# watchwinder.net
KiCad netlist of a schematic drawn in EAGLE
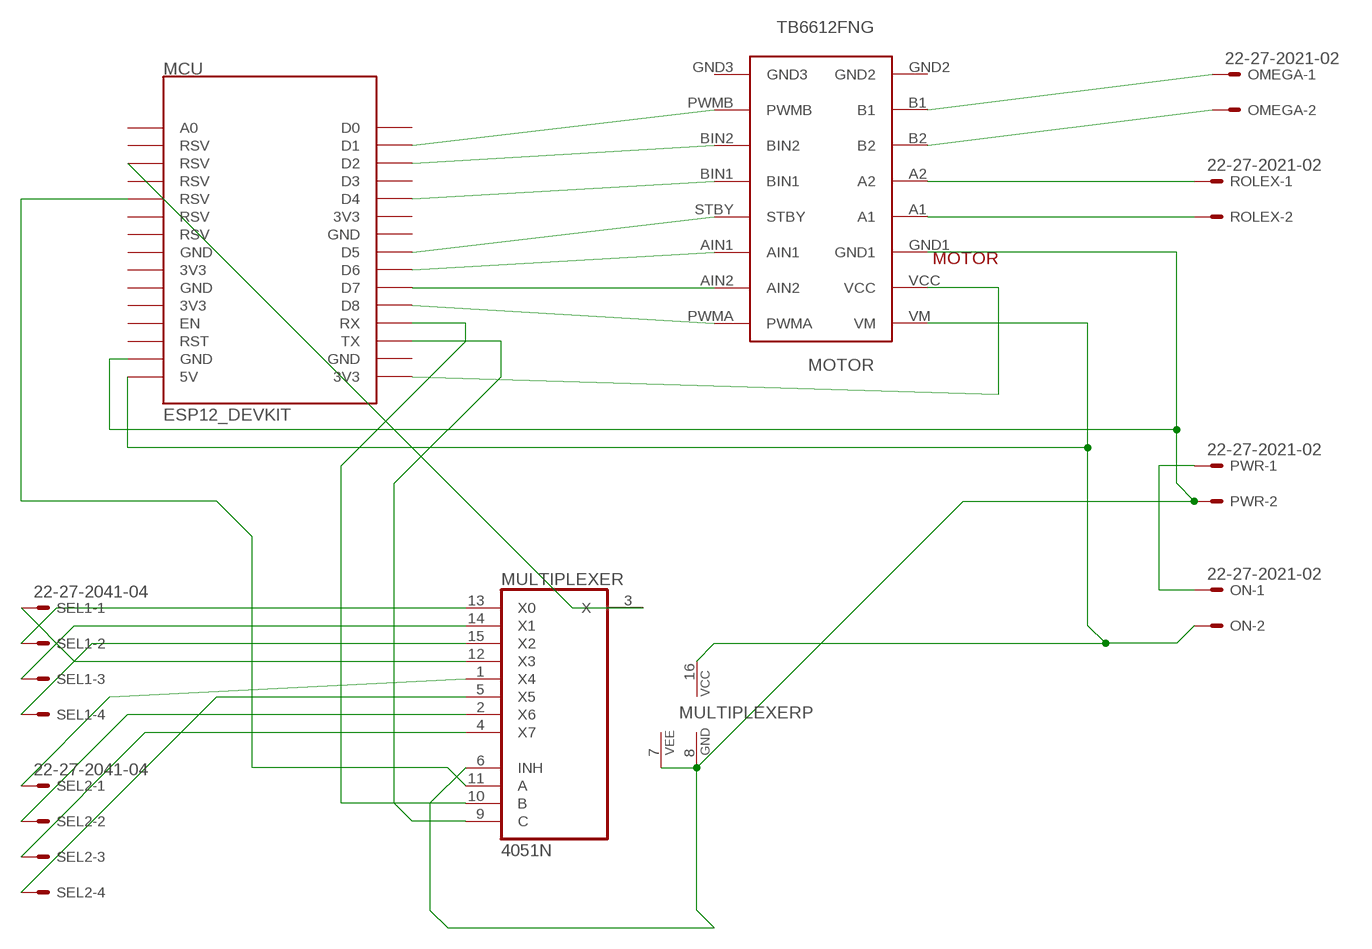
[diagram p0: schematic, sheet 1]

(export (version "E")
  (design (tool "Eeschema 10.0.6"))
  (components
    (comp (ref "MCU")
      (value "ESP12_DEVKIT")
      (footprint "eagle-import:ESP12_DEVKIT")
      (libsource (lib "eagle-import") (part "ESP12_DEVKIT"))
    )
    (comp (ref "MOTOR")
      (value "TB6612FNG")
      (footprint "eagle-import:TB6612FNG")
      (libsource (lib "eagle-import") (part "TB6612FNG"))
    )
    (comp (ref "MULTIPLEXER")
      (value "4051N")
      (footprint "eagle-import:DIL16")
      (libsource (lib "eagle-import") (part "4051N"))
    )
    (comp (ref "OMEGA")
      (value "22-27-2021-02")
      (footprint "eagle-import:6410-02")
      (libsource (lib "eagle-import") (part "22-?-0227-2021"))
    )
    (comp (ref "ON")
      (value "22-27-2021-02")
      (footprint "eagle-import:6410-02")
      (libsource (lib "eagle-import") (part "22-?-0227-2021"))
    )
    (comp (ref "PWR")
      (value "22-27-2021-02")
      (footprint "eagle-import:6410-02")
      (libsource (lib "eagle-import") (part "22-?-0227-2021"))
    )
    (comp (ref "ROLEX")
      (value "22-27-2021-02")
      (footprint "eagle-import:6410-02")
      (libsource (lib "eagle-import") (part "22-?-0227-2021"))
    )
    (comp (ref "SEL1")
      (value "22-27-2041-04")
      (footprint "eagle-import:6410-04")
      (libsource (lib "eagle-import") (part "22-?-0427-2041"))
    )
    (comp (ref "SEL2")
      (value "22-27-2041-04")
      (footprint "eagle-import:6410-04")
      (libsource (lib "eagle-import") (part "22-?-0427-2041"))
    )
  )
  (nets
    (net (code "1") (name "Net-(MCU-3V3-Pad3V3@2)") (class "Default")
      (node (ref "MCU") (pin "3V3@2") (pinfunction "3V3_3V3@2") (pintype "bidirectional"))
      (node (ref "MOTOR") (pin "VCC") (pinfunction "VCC_VCC") (pintype "bidirectional"))
    )
    (net (code "2") (name "Net-(MCU-PadD1)") (class "Default")
      (node (ref "MCU") (pin "D1") (pinfunction "D1_D1") (pintype "bidirectional"))
      (node (ref "MOTOR") (pin "PWMB") (pinfunction "PWMB_PWMB") (pintype "bidirectional"))
    )
    (net (code "3") (name "Net-(MCU-PadD2)") (class "Default")
      (node (ref "MCU") (pin "D2") (pinfunction "D2_D2") (pintype "bidirectional"))
      (node (ref "MOTOR") (pin "BIN2") (pinfunction "BIN2_BIN2") (pintype "bidirectional"))
    )
    (net (code "4") (name "Net-(MCU-PadD4)") (class "Default")
      (node (ref "MCU") (pin "D4") (pinfunction "D4_D4") (pintype "bidirectional"))
      (node (ref "MOTOR") (pin "BIN1") (pinfunction "BIN1_BIN1") (pintype "bidirectional"))
    )
    (net (code "5") (name "Net-(MCU-PadD5)") (class "Default")
      (node (ref "MCU") (pin "D5") (pinfunction "D5_D5") (pintype "bidirectional"))
      (node (ref "MOTOR") (pin "STBY") (pinfunction "STBY_STBY") (pintype "bidirectional"))
    )
    (net (code "6") (name "Net-(MCU-PadD6)") (class "Default")
      (node (ref "MCU") (pin "D6") (pinfunction "D6_D6") (pintype "bidirectional"))
      (node (ref "MOTOR") (pin "AIN1") (pinfunction "AIN1_AIN1") (pintype "bidirectional"))
    )
    (net (code "7") (name "Net-(MCU-PadD7)") (class "Default")
      (node (ref "MCU") (pin "D7") (pinfunction "D7_D7") (pintype "bidirectional"))
      (node (ref "MOTOR") (pin "AIN2") (pinfunction "AIN2_AIN2") (pintype "bidirectional"))
    )
    (net (code "8") (name "Net-(MCU-PadD8)") (class "Default")
      (node (ref "MCU") (pin "D8") (pinfunction "D8_D8") (pintype "bidirectional"))
      (node (ref "MOTOR") (pin "PWMA") (pinfunction "PWMA_PWMA") (pintype "bidirectional"))
    )
    (net (code "9") (name "Net-(MULTIPLEXERA-A)") (class "Default")
      (node (ref "MCU") (pin "RSV@3") (pinfunction "RSV_RSV@3") (pintype "bidirectional"))
      (node (ref "MULTIPLEXER") (pin "11") (pinfunction "A_11") (pintype "input"))
    )
    (net (code "10") (name "Net-(MULTIPLEXERA-B)") (class "Default")
      (node (ref "MCU") (pin "RX") (pinfunction "RX_RX") (pintype "bidirectional"))
      (node (ref "MULTIPLEXER") (pin "10") (pinfunction "B_10") (pintype "input"))
    )
    (net (code "11") (name "Net-(MULTIPLEXERA-C)") (class "Default")
      (node (ref "MCU") (pin "TX") (pinfunction "TX_TX") (pintype "bidirectional"))
      (node (ref "MULTIPLEXER") (pin "9") (pinfunction "C_9") (pintype "input"))
    )
    (net (code "12") (name "Net-(MULTIPLEXERA-INH)") (class "Default")
      (node (ref "MCU") (pin "GND@1") (pinfunction "GND_GND@1") (pintype "bidirectional"))
      (node (ref "MOTOR") (pin "GND1") (pinfunction "GND1_GND1") (pintype "bidirectional"))
      (node (ref "MULTIPLEXER") (pin "6") (pinfunction "INH_6") (pintype "input"))
      (node (ref "MULTIPLEXER") (pin "7") (pinfunction "VEE_7") (pintype "power_in"))
      (node (ref "MULTIPLEXER") (pin "8") (pinfunction "GND_8") (pintype "power_in"))
      (node (ref "PWR") (pin "2") (pinfunction "S_2") (pintype "passive"))
    )
    (net (code "13") (name "Net-(MULTIPLEXERA-X)") (class "Default")
      (node (ref "MCU") (pin "RSV@1") (pinfunction "RSV_RSV@1") (pintype "bidirectional"))
      (node (ref "MULTIPLEXER") (pin "3") (pinfunction "X_3") (pintype "bidirectional"))
    )
    (net (code "14") (name "Net-(MULTIPLEXERA-X0)") (class "Default")
      (node (ref "MULTIPLEXER") (pin "13") (pinfunction "X0_13") (pintype "bidirectional"))
      (node (ref "SEL1") (pin "2") (pinfunction "S_2") (pintype "passive"))
    )
    (net (code "15") (name "Net-(MULTIPLEXERA-X1)") (class "Default")
      (node (ref "MULTIPLEXER") (pin "14") (pinfunction "X1_14") (pintype "bidirectional"))
      (node (ref "SEL1") (pin "3") (pinfunction "S_3") (pintype "passive"))
    )
    (net (code "16") (name "Net-(MULTIPLEXERA-X2)") (class "Default")
      (node (ref "MULTIPLEXER") (pin "15") (pinfunction "X2_15") (pintype "bidirectional"))
      (node (ref "SEL1") (pin "4") (pinfunction "S_4") (pintype "passive"))
    )
    (net (code "17") (name "Net-(MULTIPLEXERA-X3)") (class "Default")
      (node (ref "MULTIPLEXER") (pin "12") (pinfunction "X3_12") (pintype "bidirectional"))
      (node (ref "SEL1") (pin "1") (pinfunction "S_1") (pintype "passive"))
    )
    (net (code "18") (name "Net-(MULTIPLEXERA-X4)") (class "Default")
      (node (ref "MULTIPLEXER") (pin "1") (pinfunction "X4_1") (pintype "bidirectional"))
      (node (ref "SEL2") (pin "1") (pinfunction "S_1") (pintype "passive"))
    )
    (net (code "19") (name "Net-(MULTIPLEXERA-X5)") (class "Default")
      (node (ref "MULTIPLEXER") (pin "5") (pinfunction "X5_5") (pintype "bidirectional"))
      (node (ref "SEL2") (pin "4") (pinfunction "S_4") (pintype "passive"))
    )
    (net (code "20") (name "Net-(MULTIPLEXERA-X6)") (class "Default")
      (node (ref "MULTIPLEXER") (pin "2") (pinfunction "X6_2") (pintype "bidirectional"))
      (node (ref "SEL2") (pin "2") (pinfunction "S_2") (pintype "passive"))
    )
    (net (code "21") (name "Net-(MULTIPLEXERA-X7)") (class "Default")
      (node (ref "MULTIPLEXER") (pin "4") (pinfunction "X7_4") (pintype "bidirectional"))
      (node (ref "SEL2") (pin "3") (pinfunction "S_3") (pintype "passive"))
    )
    (net (code "22") (name "Net-(MULTIPLEXERB-VCC)") (class "Default")
      (node (ref "MCU") (pin "5V") (pinfunction "5V_5V") (pintype "bidirectional"))
      (node (ref "MOTOR") (pin "VM") (pinfunction "VM_VM") (pintype "bidirectional"))
      (node (ref "MULTIPLEXER") (pin "16") (pinfunction "VCC_16") (pintype "power_in"))
      (node (ref "ON") (pin "2") (pinfunction "S_2") (pintype "passive"))
    )
    (net (code "23") (name "Net-(OMEGAA-S)") (class "Default")
      (node (ref "MOTOR") (pin "B1") (pinfunction "B1_B1") (pintype "bidirectional"))
      (node (ref "OMEGA") (pin "1") (pinfunction "S_1") (pintype "passive"))
    )
    (net (code "24") (name "Net-(OMEGAB-S)") (class "Default")
      (node (ref "MOTOR") (pin "B2") (pinfunction "B2_B2") (pintype "bidirectional"))
      (node (ref "OMEGA") (pin "2") (pinfunction "S_2") (pintype "passive"))
    )
    (net (code "25") (name "Net-(ONA-S)") (class "Default")
      (node (ref "ON") (pin "1") (pinfunction "S_1") (pintype "passive"))
      (node (ref "PWR") (pin "1") (pinfunction "S_1") (pintype "passive"))
    )
    (net (code "26") (name "Net-(ROLEXA-S)") (class "Default")
      (node (ref "MOTOR") (pin "A2") (pinfunction "A2_A2") (pintype "bidirectional"))
      (node (ref "ROLEX") (pin "1") (pinfunction "S_1") (pintype "passive"))
    )
    (net (code "27") (name "Net-(ROLEXB-S)") (class "Default")
      (node (ref "MOTOR") (pin "A1") (pinfunction "A1_A1") (pintype "bidirectional"))
      (node (ref "ROLEX") (pin "2") (pinfunction "S_2") (pintype "passive"))
    )
    (net (code "28") (name "unconnected-(MCU-3V3-Pad3V3@0)") (class "Default")
      (node (ref "MCU") (pin "3V3@0") (pinfunction "3V3_3V3@0") (pintype "bidirectional"))
    )
    (net (code "29") (name "unconnected-(MCU-3V3-Pad3V3@1)") (class "Default")
      (node (ref "MCU") (pin "3V3@1") (pinfunction "3V3_3V3@1") (pintype "bidirectional"))
    )
    (net (code "30") (name "unconnected-(MCU-3V3-Pad3V3@3)") (class "Default")
      (node (ref "MCU") (pin "3V3@3") (pinfunction "3V3_3V3@3") (pintype "bidirectional"))
    )
    (net (code "31") (name "unconnected-(MCU-GND-PadGND@0)") (class "Default")
      (node (ref "MCU") (pin "GND@0") (pinfunction "GND_GND@0") (pintype "bidirectional"))
    )
    (net (code "32") (name "unconnected-(MCU-GND-PadGND@2)") (class "Default")
      (node (ref "MCU") (pin "GND@2") (pinfunction "GND_GND@2") (pintype "bidirectional"))
    )
    (net (code "33") (name "unconnected-(MCU-GND-PadGND@3)") (class "Default")
      (node (ref "MCU") (pin "GND@3") (pinfunction "GND_GND@3") (pintype "bidirectional"))
    )
    (net (code "34") (name "unconnected-(MCU-GND-PadGND@4)") (class "Default")
      (node (ref "MCU") (pin "GND@4") (pinfunction "GND_GND@4") (pintype "bidirectional"))
    )
    (net (code "35") (name "unconnected-(MCU-PadA0)") (class "Default")
      (node (ref "MCU") (pin "A0") (pinfunction "A0_A0") (pintype "bidirectional"))
    )
    (net (code "36") (name "unconnected-(MCU-PadD0)") (class "Default")
      (node (ref "MCU") (pin "D0") (pinfunction "D0_D0") (pintype "bidirectional"))
    )
    (net (code "37") (name "unconnected-(MCU-PadD3)") (class "Default")
      (node (ref "MCU") (pin "D3") (pinfunction "D3_D3") (pintype "bidirectional"))
    )
    (net (code "38") (name "unconnected-(MCU-PadEN)") (class "Default")
      (node (ref "MCU") (pin "EN") (pinfunction "EN_EN") (pintype "bidirectional"))
    )
    (net (code "39") (name "unconnected-(MCU-PadRST)") (class "Default")
      (node (ref "MCU") (pin "RST") (pinfunction "RST_RST") (pintype "bidirectional"))
    )
    (net (code "40") (name "unconnected-(MCU-RSV-PadRSV@0)") (class "Default")
      (node (ref "MCU") (pin "RSV@0") (pinfunction "RSV_RSV@0") (pintype "bidirectional"))
    )
    (net (code "41") (name "unconnected-(MCU-RSV-PadRSV@2)") (class "Default")
      (node (ref "MCU") (pin "RSV@2") (pinfunction "RSV_RSV@2") (pintype "bidirectional"))
    )
    (net (code "42") (name "unconnected-(MCU-RSV-PadRSV@4)") (class "Default")
      (node (ref "MCU") (pin "RSV@4") (pinfunction "RSV_RSV@4") (pintype "bidirectional"))
    )
    (net (code "43") (name "unconnected-(MCU-RSV-PadRSV@5)") (class "Default")
      (node (ref "MCU") (pin "RSV@5") (pinfunction "RSV_RSV@5") (pintype "bidirectional"))
    )
    (net (code "44") (name "unconnected-(MOTOR-PadGND2)") (class "Default")
      (node (ref "MOTOR") (pin "GND2") (pinfunction "GND2_GND2") (pintype "bidirectional"))
    )
    (net (code "45") (name "unconnected-(MOTOR-PadGND3)") (class "Default")
      (node (ref "MOTOR") (pin "GND3") (pinfunction "GND3_GND3") (pintype "bidirectional"))
    )
  )
)
